# RS485.net
KiCad netlist of a schematic drawn in Altium Designer
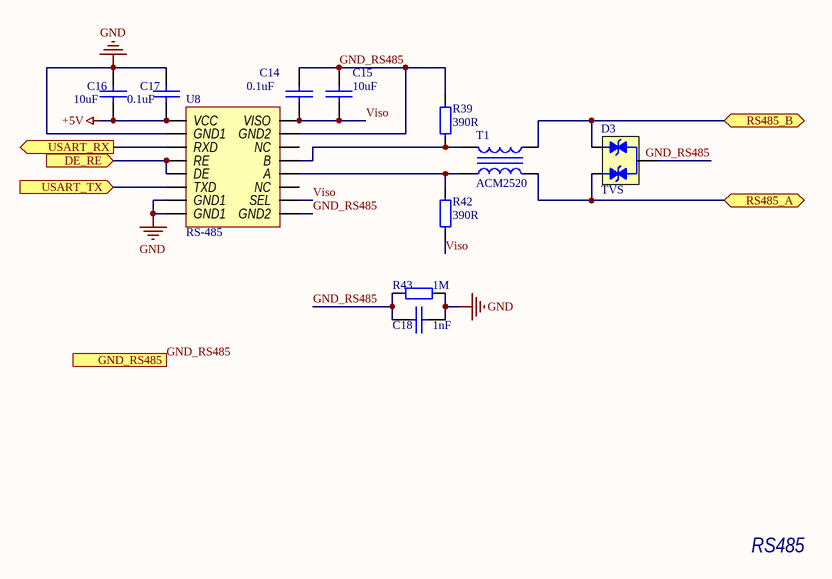
[diagram p0: RS485.SchDoc]

(export (version "E")
  (design (tool "Eeschema 10.0.6"))
  (components
    (comp (ref "C14")
      (value "0.1uF")
      (footprint "0603 Capicator")
      (description "0.1uF X7R 16V 10% 0603")
      (fields
        (field (name "MANUFACTURER") "Murata Manufacturing")
        (field (name "PART NUMBER") "GRM188R71C104KA01D")
      )
      (libsource (lib "БУС") (part "Cap 0.1uF (0603)"))
    )
    (comp (ref "C15")
      (value "10uF")
      (footprint "0603 Capicator")
      (description "10uF X5R 25V 20% 0603")
      (fields
        (field (name "MANUFACTURER") "Murata Manufacturing")
        (field (name "PART NUMBER") "GRM188R61E106M")
      )
      (libsource (lib "БУС") (part "Cap 10uF (0603)"))
    )
    (comp (ref "C16")
      (value "10uF")
      (footprint "0603 Capicator")
      (description "10uF X5R 25V 20% 0603")
      (fields
        (field (name "MANUFACTURER") "Murata Manufacturing")
        (field (name "PART NUMBER") "GRM188R61E106M")
      )
      (libsource (lib "БУС") (part "Cap 10uF (0603)"))
    )
    (comp (ref "C17")
      (value "0.1uF")
      (footprint "0603 Capicator")
      (description "0.1uF X7R 16V 10% 0603")
      (fields
        (field (name "MANUFACTURER") "Murata Manufacturing")
        (field (name "PART NUMBER") "GRM188R71C104KA01D")
      )
      (libsource (lib "БУС") (part "Cap 0.1uF (0603)"))
    )
    (comp (ref "C18")
      (value "1nF")
      (footprint "0603 Capicator")
      (description "X7R 1nF 100V 10% 0603")
      (fields
        (field (name "MANUFACTURER") "Murata Manufacturing")
        (field (name "PART NUMBER") "GRM188R72A102KA01D")
      )
      (libsource (lib "БУС") (part "Cap 1nF (0603)"))
    )
    (comp (ref "D3")
      (value "TVS")
      (footprint "SOT-23")
      (fields (field (name "PART NUMBER") "SM24CANB-02HTG") (field (name "MANUFACTURER") "Littelfuse"))
      (libsource (lib "БУС") (part "TVS Diode Arrays"))
    )
    (comp (ref "R39")
      (value "390R")
      (footprint "1206 RESISTOR")
      (description "0.25W 1206 390R")
      (fields (field (name "PART NUMBER") "RC1206JR-07390KL") (field (name "MANUFACTURER") "Taiwan"))
      (libsource (lib "БУС") (part "Res 390R (1206)"))
    )
    (comp (ref "R42")
      (value "390R")
      (footprint "1206 RESISTOR")
      (description "0.25W 1206 390R")
      (fields (field (name "PART NUMBER") "RC1206JR-07390KL") (field (name "MANUFACTURER") "Taiwan"))
      (libsource (lib "БУС") (part "Res 390R (1206)"))
    )
    (comp (ref "R43")
      (value "1M")
      (footprint "0603 Resistor")
      (description "0.1W 0603 1M, 1%")
      (fields (field (name "PART NUMBER") "RC0603FR-071ML") (field (name "MANUFACTURER") "Taiwan"))
      (libsource (lib "БУС") (part "Res 1M (0603)"))
    )
    (comp (ref "T1")
      (value "ACM2520")
      (footprint "ACM2520")
      (description "Common mode filters\r\nAutomotive signal line (for power train/safety)")
      (fields (field (name "MANUFACTURER") "TDK") (field (name "PART NUMBER") "ACM2520-301-2P-T002"))
      (libsource (lib "БУС") (part "ACM2520"))
    )
    (comp (ref "U8")
      (value "RS-485")
      (footprint "SOIC16W")
      (description "Isolated RS-485 Half-Duplex tranciever")
      (fields (field (name "MANUFACTURER") "Mornsun") (field (name "PART NUMBER") "TDA51S485HC"))
      (libsource (lib "БУС") (part "TDA51S485HC"))
    )
  )
  (nets
    (net (code "1") (name "+5V") (class "Default")
      (node (ref "C16") (pin "2") (pinfunction "2_2") (pintype "passive"))
      (node (ref "C17") (pin "1") (pinfunction "1_1") (pintype "passive"))
      (node (ref "U8") (pin "1") (pinfunction "VCC_1") (pintype "passive"))
    )
    (net (code "2") (name "/DE_RE") (class "Default")
      (node (ref "U8") (pin "4") (pinfunction "RE_4") (pintype "passive"))
      (node (ref "U8") (pin "5") (pinfunction "DE_5") (pintype "passive"))
    )
    (net (code "3") (name "/GND_RS485") (class "Default")
      (node (ref "C14") (pin "2") (pinfunction "2_2") (pintype "passive"))
      (node (ref "C15") (pin "2") (pinfunction "2_2") (pintype "passive"))
      (node (ref "C18") (pin "1") (pinfunction "1_1") (pintype "passive"))
      (node (ref "D3") (pin "3") (pinfunction "3_3") (pintype "passive"))
      (node (ref "R39") (pin "2") (pinfunction "2_2") (pintype "passive"))
      (node (ref "R43") (pin "1") (pinfunction "1_1") (pintype "passive"))
      (node (ref "U8") (pin "15") (pinfunction "GND2_15") (pintype "passive"))
      (node (ref "U8") (pin "9") (pinfunction "GND2_9") (pintype "passive"))
    )
    (net (code "4") (name "/RS485_A") (class "Default")
      (node (ref "D3") (pin "2") (pinfunction "2_2") (pintype "passive"))
      (node (ref "T1") (pin "3") (pinfunction "3_3") (pintype "passive"))
    )
    (net (code "5") (name "/RS485_B") (class "Default")
      (node (ref "D3") (pin "1") (pinfunction "1_1") (pintype "passive"))
      (node (ref "T1") (pin "4") (pinfunction "4_4") (pintype "passive"))
    )
    (net (code "6") (name "/USART_RX") (class "Default")
      (node (ref "U8") (pin "3") (pinfunction "RXD_3") (pintype "passive"))
    )
    (net (code "7") (name "/USART_TX") (class "Default")
      (node (ref "U8") (pin "6") (pinfunction "TXD_6") (pintype "passive"))
    )
    (net (code "8") (name "/Viso") (class "Default")
      (node (ref "C14") (pin "1") (pinfunction "1_1") (pintype "passive"))
      (node (ref "C15") (pin "1") (pinfunction "1_1") (pintype "passive"))
      (node (ref "R42") (pin "1") (pinfunction "1_1") (pintype "passive"))
      (node (ref "U8") (pin "10") (pinfunction "SEL_10") (pintype "passive"))
      (node (ref "U8") (pin "16") (pinfunction "VISO_16") (pintype "passive"))
    )
    (net (code "9") (name "GND") (class "Default")
      (node (ref "C16") (pin "1") (pinfunction "1_1") (pintype "passive"))
      (node (ref "C17") (pin "2") (pinfunction "2_2") (pintype "passive"))
      (node (ref "C18") (pin "2") (pinfunction "2_2") (pintype "passive"))
      (node (ref "R43") (pin "2") (pinfunction "2_2") (pintype "passive"))
      (node (ref "U8") (pin "2") (pinfunction "GND1_2") (pintype "passive"))
      (node (ref "U8") (pin "7") (pinfunction "GND1_7") (pintype "passive"))
      (node (ref "U8") (pin "8") (pinfunction "GND1_8") (pintype "passive"))
    )
    (net (code "10") (name "Net-(U8-A)") (class "Default")
      (node (ref "R42") (pin "2") (pinfunction "2_2") (pintype "passive"))
      (node (ref "T1") (pin "2") (pinfunction "2_2") (pintype "passive"))
      (node (ref "U8") (pin "12") (pinfunction "A_12") (pintype "passive"))
    )
    (net (code "11") (name "Net-(U8-B)") (class "Default")
      (node (ref "R39") (pin "1") (pinfunction "1_1") (pintype "passive"))
      (node (ref "T1") (pin "1") (pinfunction "1_1") (pintype "passive"))
      (node (ref "U8") (pin "13") (pinfunction "B_13") (pintype "passive"))
    )
    (net (code "12") (name "unconnected-(U8-NC-Pad11)") (class "Default")
      (node (ref "U8") (pin "11") (pinfunction "NC_11") (pintype "passive"))
    )
    (net (code "13") (name "unconnected-(U8-NC-Pad14)") (class "Default")
      (node (ref "U8") (pin "14") (pinfunction "NC_14") (pintype "passive"))
    )
  )
)
